# TH_Sensor_Output_Socket.net
KiCad netlist of a schematic drawn in Altium Designer
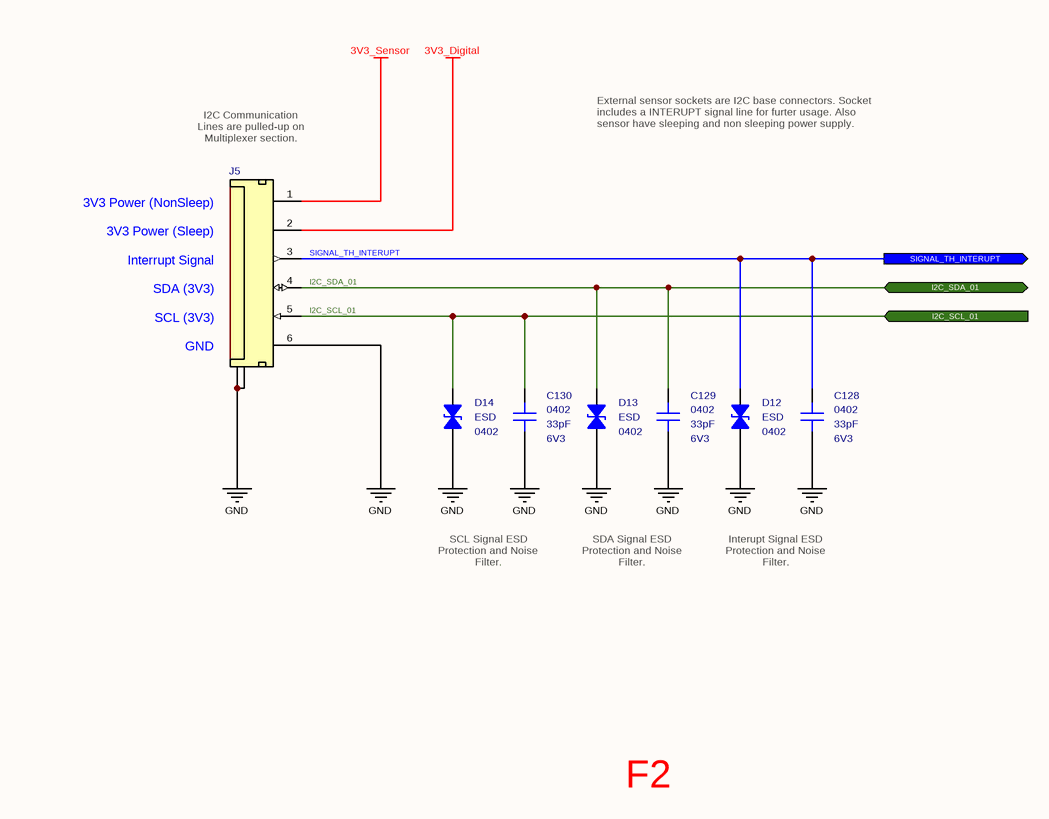
[diagram p0: TH Sensor Output Socket.SchDoc]

(export (version "E")
  (design (tool "Eeschema 10.0.6"))
  (components
    (comp (ref "C128")
      (value "33pF")
      (footprint "CAPACITOR_0402")
      (description "Capacitor - 33pF [0402] (Ceramic)")
      (fields
        (field (name "MANUFACTURER_PART_NUMBER") "C0402C330J9RACAUTO")
        (field (name "MOUSER_PART_NUMBER") "80-C0402C330J9RAUTO")
        (field (name "CASE") "0402")
        (field (name "VOLTAGE") "6V3")
      )
      (libsource (lib "Ovoo_Schematic") (part "Capacitor - 33pF [0402-6V3]"))
    )
    (comp (ref "C129")
      (value "33pF")
      (footprint "CAPACITOR_0402")
      (description "Capacitor - 33pF [0402] (Ceramic)")
      (fields
        (field (name "MANUFACTURER_PART_NUMBER") "C0402C330J9RACAUTO")
        (field (name "MOUSER_PART_NUMBER") "80-C0402C330J9RAUTO")
        (field (name "CASE") "0402")
        (field (name "VOLTAGE") "6V3")
      )
      (libsource (lib "Ovoo_Schematic") (part "Capacitor - 33pF [0402-6V3]"))
    )
    (comp (ref "C130")
      (value "33pF")
      (footprint "CAPACITOR_0402")
      (description "Capacitor - 33pF [0402] (Ceramic)")
      (fields
        (field (name "MANUFACTURER_PART_NUMBER") "C0402C330J9RACAUTO")
        (field (name "MOUSER_PART_NUMBER") "80-C0402C330J9RAUTO")
        (field (name "CASE") "0402")
        (field (name "VOLTAGE") "6V3")
      )
      (libsource (lib "Ovoo_Schematic") (part "Capacitor - 33pF [0402-6V3]"))
    )
    (comp (ref "D12")
      (value "ESD Suppressors")
      (footprint "ESD_0402")
      (description "TVS Diode (Bi-directional)")
      (fields
        (field (name "MANUFACTURER_PART_NUMBER") "0402ESDA-MLP1")
        (field (name "MOUSER_PART_NUMBER") "504-0402ESDA-MLP1")
        (field (name "CASE") "0402")
      )
      (libsource (lib "Ovoo_Schematic") (part "Diode - ESD Protection"))
    )
    (comp (ref "D13")
      (value "ESD Suppressors")
      (footprint "ESD_0402")
      (description "TVS Diode (Bi-directional)")
      (fields
        (field (name "MANUFACTURER_PART_NUMBER") "0402ESDA-MLP1")
        (field (name "MOUSER_PART_NUMBER") "504-0402ESDA-MLP1")
        (field (name "CASE") "0402")
      )
      (libsource (lib "Ovoo_Schematic") (part "Diode - ESD Protection"))
    )
    (comp (ref "D14")
      (value "ESD Suppressors")
      (footprint "ESD_0402")
      (description "TVS Diode (Bi-directional)")
      (fields
        (field (name "MANUFACTURER_PART_NUMBER") "0402ESDA-MLP1")
        (field (name "MOUSER_PART_NUMBER") "504-0402ESDA-MLP1")
        (field (name "CASE") "0402")
      )
      (libsource (lib "Ovoo_Schematic") (part "Diode - ESD Protection"))
    )
    (comp (ref "J5")
      (value "T/H Sensor Socket")
      (footprint "Connector_Tunic 6P - H")
      (description "Mini Tunic Connector with 6P")
      (fields (field (name "MANUFACTURER_PART_NUMBER") "53261-0671"))
      (libsource (lib "Ovoo_Schematic") (part "Connector - Mini Tunic 6P (1.25)"))
    )
  )
  (nets
    (net (code "1") (name "/I2C_SCL_01") (class "Default")
      (node (ref "C130") (pin "2") (pinfunction "2_2") (pintype "passive"))
      (node (ref "D14") (pin "2") (pinfunction "2_2") (pintype "passive"))
      (node (ref "J5") (pin "5") (pinfunction "SCL01_5") (pintype "input"))
    )
    (net (code "2") (name "/I2C_SDA_01") (class "Default")
      (node (ref "C129") (pin "2") (pinfunction "2_2") (pintype "passive"))
      (node (ref "D13") (pin "2") (pinfunction "2_2") (pintype "passive"))
      (node (ref "J5") (pin "4") (pinfunction "SDA01_4") (pintype "bidirectional"))
    )
    (net (code "3") (name "/SIGNAL_TH_INTERUPT") (class "Default")
      (node (ref "C128") (pin "2") (pinfunction "2_2") (pintype "passive"))
      (node (ref "D12") (pin "2") (pinfunction "2_2") (pintype "passive"))
      (node (ref "J5") (pin "3") (pinfunction "TH_Interupt_3") (pintype "output"))
    )
    (net (code "4") (name "3V3_Digital") (class "Default")
      (node (ref "J5") (pin "2") (pinfunction "3V3_Digital_2") (pintype "power_in"))
    )
    (net (code "5") (name "3V3_Sensor") (class "Default")
      (node (ref "J5") (pin "1") (pinfunction "3V3_Sensor_1") (pintype "power_in"))
    )
    (net (code "6") (name "GND") (class "Default")
      (node (ref "C128") (pin "1") (pinfunction "1_1") (pintype "passive"))
      (node (ref "C129") (pin "1") (pinfunction "1_1") (pintype "passive"))
      (node (ref "C130") (pin "1") (pinfunction "1_1") (pintype "passive"))
      (node (ref "D12") (pin "1") (pinfunction "1_1") (pintype "passive"))
      (node (ref "D13") (pin "1") (pinfunction "1_1") (pintype "passive"))
      (node (ref "D14") (pin "1") (pinfunction "1_1") (pintype "passive"))
      (node (ref "J5") (pin "6") (pinfunction "GND_6") (pintype "power_in"))
      (node (ref "J5") (pin "7") (pinfunction "Termination_7") (pintype "power_in"))
      (node (ref "J5") (pin "8") (pinfunction "Termination_8") (pintype "power_in"))
    )
  )
)
